# Board-RS485.net
KiCad netlist of a schematic drawn in Altium Designer
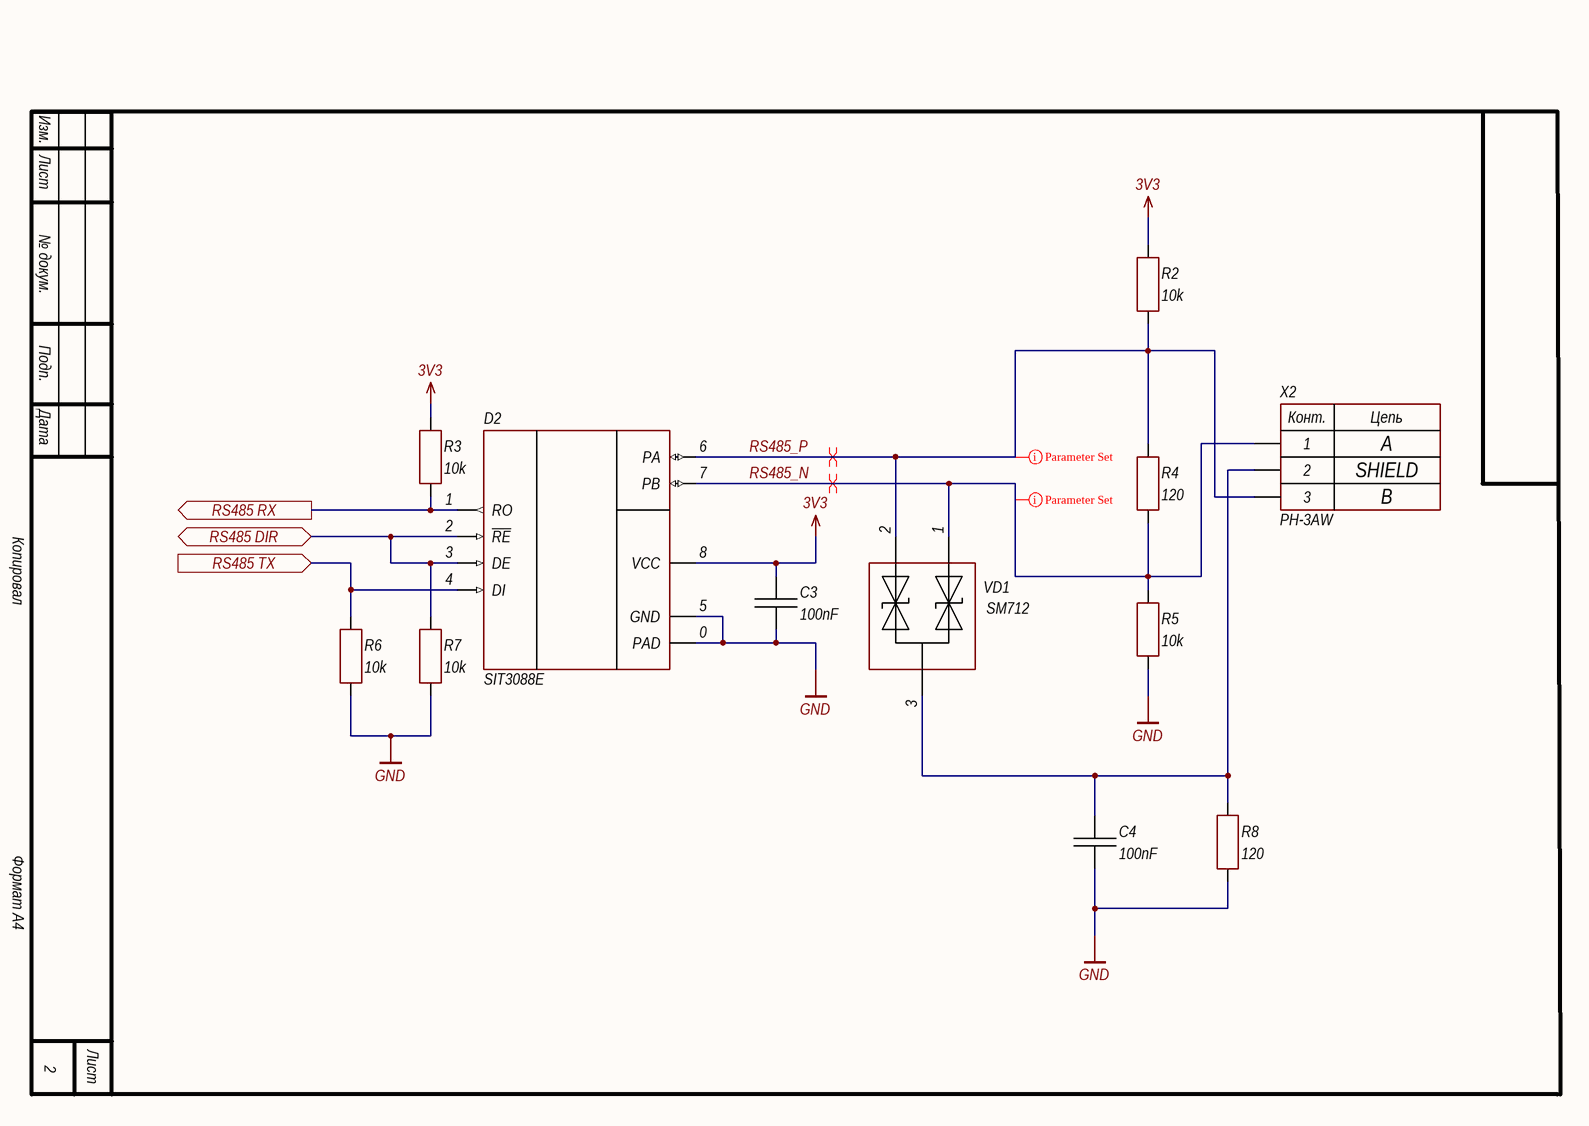
[diagram p0: Board-RS485.SchDoc]

(export (version "E")
  (design (tool "Eeschema 10.0.6"))
  (components
    (comp (ref "C3")
      (value "100nF")
      (footprint "CH0402C")
      (fields (field (name "MANUFACTURER") "CCTC"))
      (libsource (lib "Discrete") (part "Capacitor"))
    )
    (comp (ref "C4")
      (value "100nF")
      (footprint "CH0402C")
      (fields (field (name "MANUFACTURER") "CCTC"))
      (libsource (lib "Discrete") (part "Capacitor"))
    )
    (comp (ref "D2")
      (value "SIT3088E")
      (footprint "8-DFN (3x3 mm, 0.65mm pitch)")
      (description "RS485/RS422")
      (fields (field (name "MANUFACTURER") "SIT"))
      (libsource (lib "Interface") (part "SIT3088E"))
    )
    (comp (ref "R2")
      (value "10k")
      (footprint "CH0402R")
      (fields (field (name "MANUFACTURER") "Uniroyal Elec"))
      (libsource (lib "Discrete") (part "Resistor"))
    )
    (comp (ref "R3")
      (value "10k")
      (footprint "CH0402R")
      (fields (field (name "MANUFACTURER") "Uniroyal Elec"))
      (libsource (lib "Discrete") (part "Resistor"))
    )
    (comp (ref "R4")
      (value "120")
      (footprint "CH0402R")
      (fields (field (name "MANUFACTURER") "YAGEO"))
      (libsource (lib "Discrete") (part "Resistor"))
    )
    (comp (ref "R5")
      (value "10k")
      (footprint "CH0402R")
      (fields (field (name "MANUFACTURER") "Uniroyal Elec"))
      (libsource (lib "Discrete") (part "Resistor"))
    )
    (comp (ref "R6")
      (value "10k")
      (footprint "CH0402R")
      (fields (field (name "MANUFACTURER") "Uniroyal Elec"))
      (libsource (lib "Discrete") (part "Resistor"))
    )
    (comp (ref "R7")
      (value "10k")
      (footprint "CH0402R")
      (fields (field (name "MANUFACTURER") "Uniroyal Elec"))
      (libsource (lib "Discrete") (part "Resistor"))
    )
    (comp (ref "R8")
      (value "120")
      (footprint "CH0402R")
      (fields (field (name "MANUFACTURER") "YAGEO"))
      (libsource (lib "Discrete") (part "Resistor"))
    )
    (comp (ref "VD1")
      (value "SM712")
      (footprint "SOT23_132")
      (fields (field (name "MANUFACTURER") "TECH PUBLIC"))
      (libsource (lib "Diods") (part "TVS Array"))
    )
    (comp (ref "X2")
      (value "PH-3AW")
      (footprint "CON: PH-3AW")
      (libsource (lib "Connectors") (part "3-Connector"))
    )
  )
  (nets
    (net (code "1") (name "/RS485 DIR") (class "Default")
      (node (ref "D2") (pin "2") (pinfunction "~{RE}_2") (pintype "input"))
      (node (ref "D2") (pin "3") (pinfunction "DE_3") (pintype "input"))
      (node (ref "R7") (pin "2") (pinfunction "2_2") (pintype "passive"))
    )
    (net (code "2") (name "/RS485 RX") (class "Default")
      (node (ref "D2") (pin "1") (pinfunction "RO_1") (pintype "output"))
      (node (ref "R3") (pin "1") (pinfunction "1_1") (pintype "passive"))
    )
    (net (code "3") (name "/RS485 TX") (class "Default")
      (node (ref "D2") (pin "4") (pinfunction "DI_4") (pintype "input"))
      (node (ref "R6") (pin "2") (pinfunction "2_2") (pintype "passive"))
    )
    (net (code "4") (name "/RS485_N") (class "Default")
      (node (ref "D2") (pin "7") (pinfunction "PB_7") (pintype "bidirectional"))
      (node (ref "R4") (pin "1") (pinfunction "1_1") (pintype "passive"))
      (node (ref "R5") (pin "2") (pinfunction "2_2") (pintype "passive"))
      (node (ref "VD1") (pin "1") (pinfunction "1_1") (pintype "passive"))
      (node (ref "X2") (pin "1") (pinfunction "1_1") (pintype "passive"))
    )
    (net (code "5") (name "/RS485_P") (class "Default")
      (node (ref "D2") (pin "6") (pinfunction "PA_6") (pintype "bidirectional"))
      (node (ref "R2") (pin "1") (pinfunction "1_1") (pintype "passive"))
      (node (ref "R4") (pin "2") (pinfunction "2_2") (pintype "passive"))
      (node (ref "VD1") (pin "2") (pinfunction "2_2") (pintype "passive"))
      (node (ref "X2") (pin "3") (pinfunction "3_3") (pintype "passive"))
    )
    (net (code "6") (name "3V3") (class "Default")
      (node (ref "C3") (pin "2") (pinfunction "2_2") (pintype "power_in"))
      (node (ref "D2") (pin "8") (pinfunction "VCC_8") (pintype "power_in"))
      (node (ref "R2") (pin "2") (pinfunction "2_2") (pintype "passive"))
      (node (ref "R3") (pin "2") (pinfunction "2_2") (pintype "passive"))
    )
    (net (code "7") (name "GND") (class "Default")
      (node (ref "C3") (pin "1") (pinfunction "1_1") (pintype "power_in"))
      (node (ref "C4") (pin "1") (pinfunction "1_1") (pintype "power_in"))
      (node (ref "D2") (pin "0") (pinfunction "PAD_0") (pintype "power_in"))
      (node (ref "D2") (pin "5") (pinfunction "GND_5") (pintype "power_in"))
      (node (ref "R5") (pin "1") (pinfunction "1_1") (pintype "passive"))
      (node (ref "R6") (pin "1") (pinfunction "1_1") (pintype "passive"))
      (node (ref "R7") (pin "1") (pinfunction "1_1") (pintype "passive"))
      (node (ref "R8") (pin "1") (pinfunction "1_1") (pintype "passive"))
    )
    (net (code "8") (name "Net-(C4-Pad2)") (class "Default")
      (node (ref "C4") (pin "2") (pinfunction "2_2") (pintype "power_in"))
      (node (ref "R8") (pin "2") (pinfunction "2_2") (pintype "passive"))
      (node (ref "VD1") (pin "3") (pinfunction "3_3") (pintype "passive"))
      (node (ref "X2") (pin "2") (pinfunction "2_2") (pintype "passive"))
    )
  )
)
